# Maduino_Power_Line_Modem_v1_2.net
KiCad netlist of a schematic drawn in EAGLE
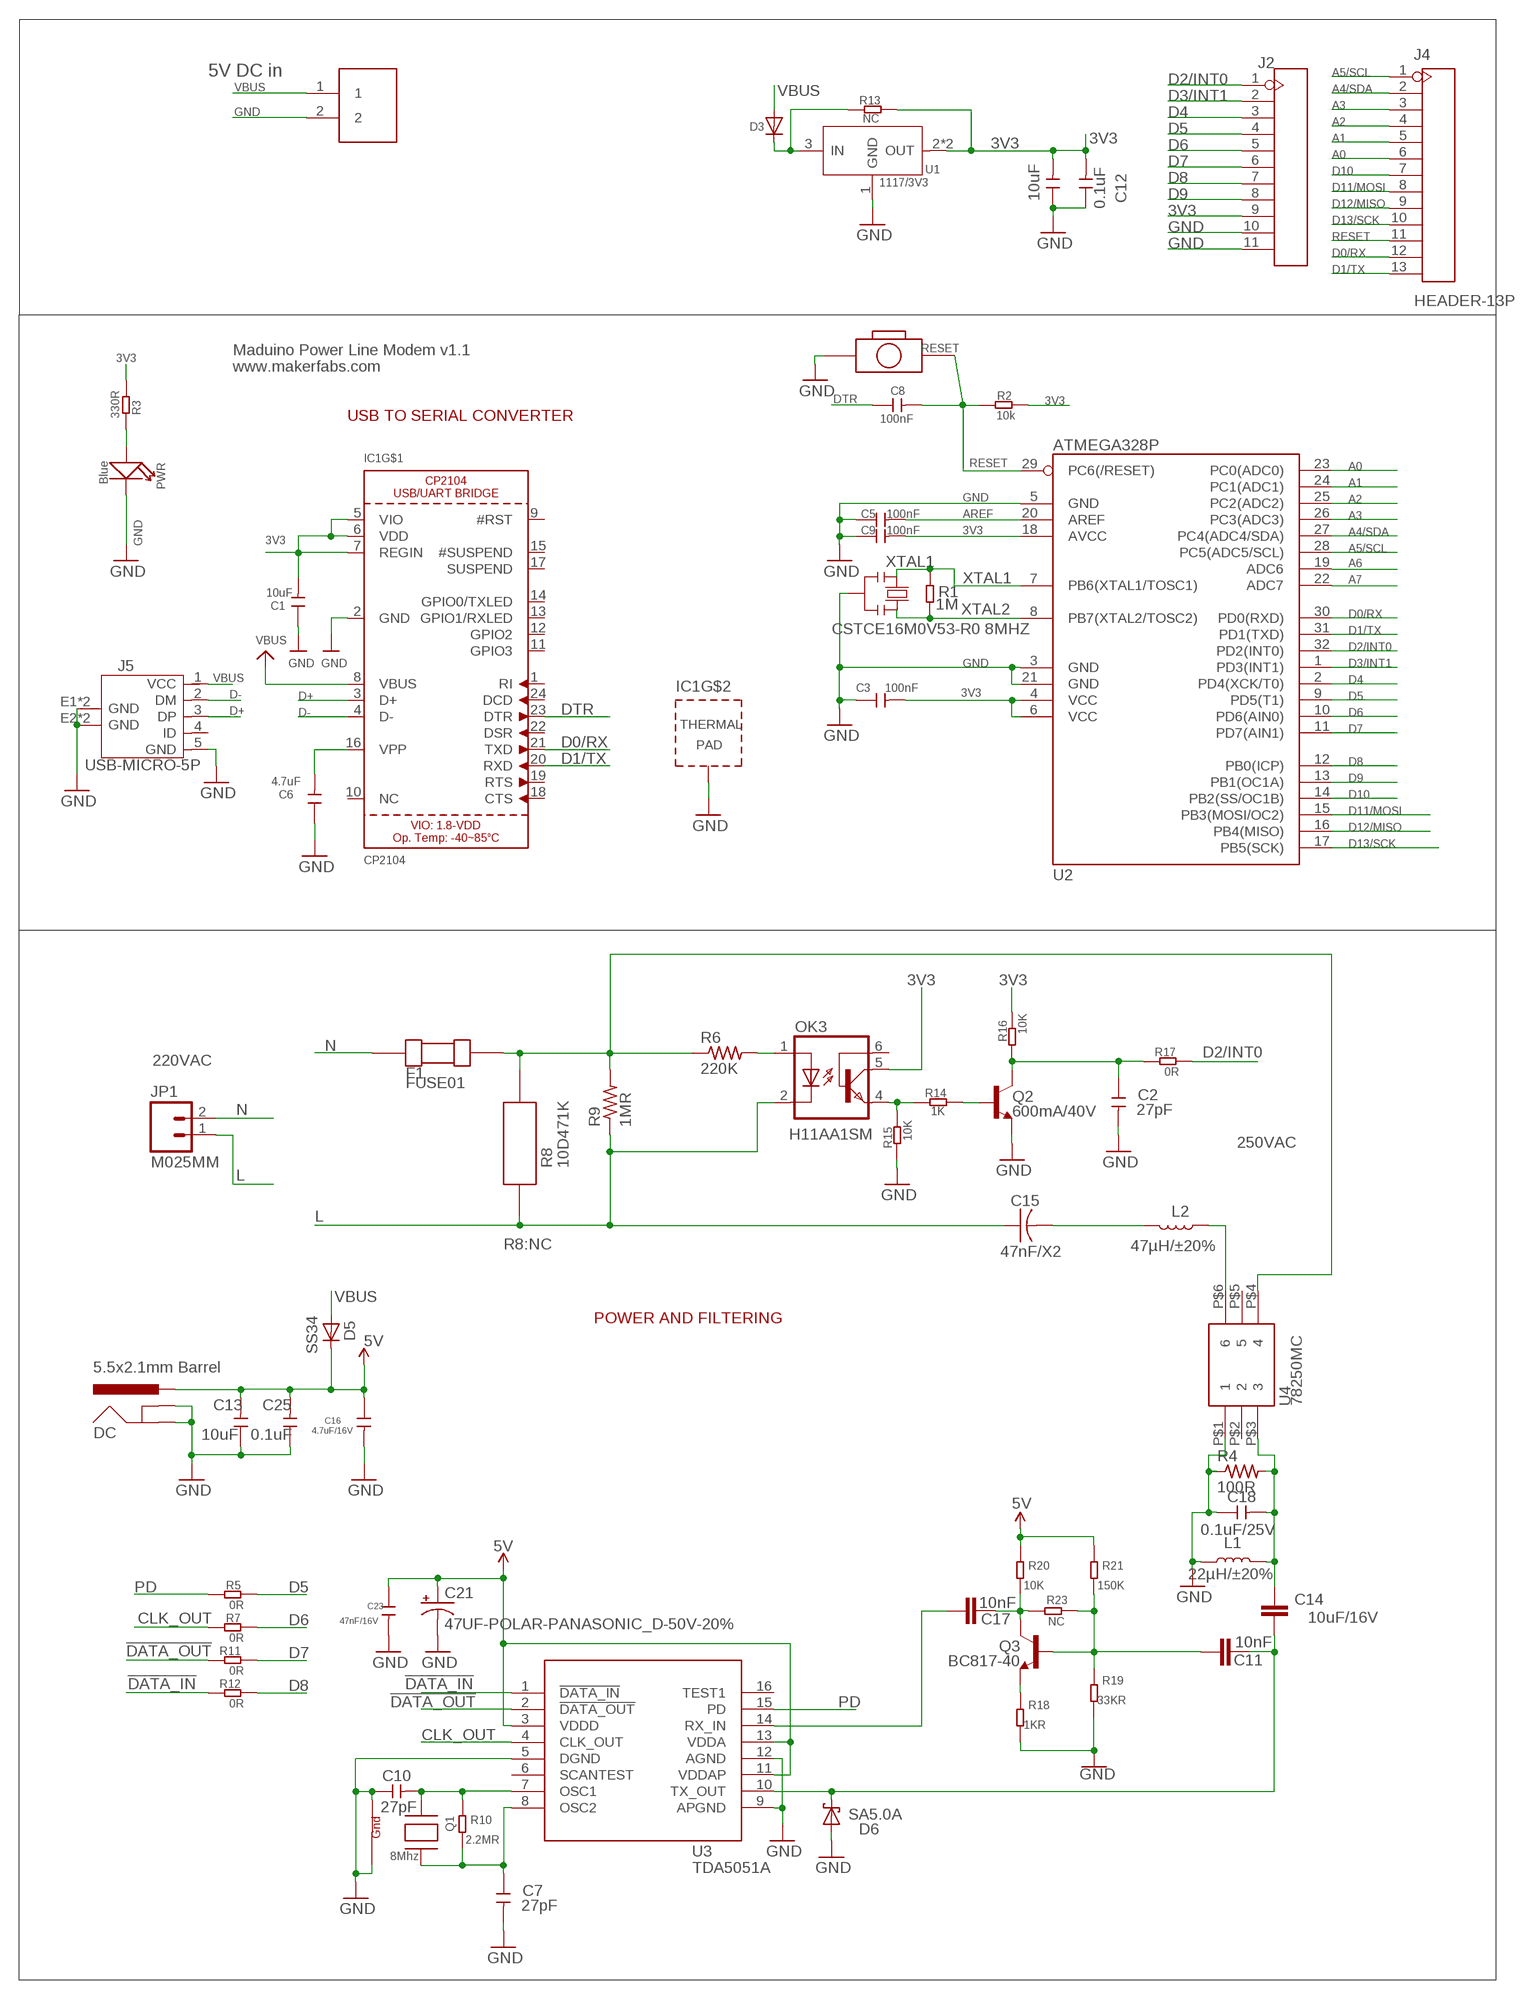
[diagram p0: schematic, sheet 1]

(export (version "E")
  (design (tool "Eeschema 10.0.6"))
  (components
    (comp (ref "C1")
      (value "10uF")
      (footprint "eagle-import:0603")
      (libsource (lib "eagle-import") (part "C-0603"))
    )
    (comp (ref "C2")
      (value "27pF")
      (footprint "eagle-import:0603")
      (libsource (lib "eagle-import") (part "C-0603"))
    )
    (comp (ref "C3")
      (value "100nF")
      (footprint "eagle-import:0603")
      (libsource (lib "eagle-import") (part "C-0603"))
    )
    (comp (ref "C4")
      (value "10uF")
      (footprint "eagle-import:0603")
      (libsource (lib "eagle-import") (part "C-0603"))
    )
    (comp (ref "C5")
      (value "100nF")
      (footprint "eagle-import:0603")
      (libsource (lib "eagle-import") (part "C-0603"))
    )
    (comp (ref "C6")
      (value "4.7uF")
      (footprint "eagle-import:0603")
      (libsource (lib "eagle-import") (part "C-0603"))
    )
    (comp (ref "C7")
      (value "27pF")
      (footprint "eagle-import:0603")
      (libsource (lib "eagle-import") (part "C-0603"))
    )
    (comp (ref "C8")
      (value "100nF")
      (footprint "eagle-import:0603")
      (libsource (lib "eagle-import") (part "C-0603"))
    )
    (comp (ref "C9")
      (value "100nF")
      (footprint "eagle-import:0603")
      (libsource (lib "eagle-import") (part "C-0603"))
    )
    (comp (ref "C10")
      (value "27pF")
      (footprint "eagle-import:0603")
      (libsource (lib "eagle-import") (part "C-0603"))
    )
    (comp (ref "C11")
      (value "10nF")
      (footprint "eagle-import:0603")
      (libsource (lib "eagle-import") (part "10NF-0603-50V-10%"))
    )
    (comp (ref "C12")
      (value "0.1uF")
      (footprint "eagle-import:0603")
      (libsource (lib "eagle-import") (part "C-0603"))
    )
    (comp (ref "C13")
      (value "10uF")
      (footprint "eagle-import:0603")
      (libsource (lib "eagle-import") (part "C-0603"))
    )
    (comp (ref "C14")
      (value "10uF/16V")
      (footprint "eagle-import:0603")
      (fields (field (name "PROD_ID") "CAP-00867"))
      (libsource (lib "eagle-import") (part "10NF-0603-50V-10%"))
    )
    (comp (ref "C15")
      (value "47nF/X2")
      (footprint "eagle-import:C150-054X183")
      (libsource (lib "eagle-import") (part "C-US150-054X183"))
    )
    (comp (ref "C16")
      (value "4.7uF/16V")
      (footprint "eagle-import:0603")
      (libsource (lib "eagle-import") (part "C-0603"))
    )
    (comp (ref "C17")
      (value "10nF")
      (footprint "eagle-import:0603")
      (fields (field (name "PROD_ID") "CAP-00867"))
      (libsource (lib "eagle-import") (part "10NF-0603-50V-10%"))
    )
    (comp (ref "C18")
      (value "0.1uF/25V")
      (footprint "eagle-import:0603")
      (libsource (lib "eagle-import") (part "C-0603"))
    )
    (comp (ref "C21")
      (value "47UF-POLAR-PANASONIC_D-50V-20%")
      (footprint "eagle-import:PANASONIC_D")
      (libsource (lib "eagle-import") (part "47UF-POLAR-PANASONIC_D-50V-20%"))
    )
    (comp (ref "C23")
      (value "47nF/16V")
      (footprint "eagle-import:0603")
      (libsource (lib "eagle-import") (part "C-0603"))
    )
    (comp (ref "C25")
      (value "0.1uF")
      (footprint "eagle-import:0603")
      (libsource (lib "eagle-import") (part "C-0603"))
    )
    (comp (ref "D3")
      (value "DIODESOD-323F")
      (footprint "eagle-import:SOD-323F")
      (libsource (lib "eagle-import") (part "DIODESOD-323F"))
    )
    (comp (ref "D5")
      (value "SS34")
      (footprint "eagle-import:DO-214AC")
      (libsource (lib "eagle-import") (part "DIODE-DO-214AC"))
    )
    (comp (ref "D6")
      (value "SA5.0A")
      (footprint "eagle-import:DO41-10")
      (libsource (lib "eagle-import") (part "SCHOTTKY-DIODEDO41"))
    )
    (comp (ref "DC")
      (value "5.5x2.1mm Barrel")
      (footprint "eagle-import:POWER_JACK_SMD")
      (libsource (lib "eagle-import") (part "POWER_JACKSMD"))
    )
    (comp (ref "F1")
      (value "FUSE01")
      (footprint "eagle-import:FUSE01")
      (libsource (lib "eagle-import") (part "FUSE01"))
    )
    (comp (ref "IC1")
      (value "CP2104")
      (footprint "eagle-import:QFN24_4MM_SMSC")
      (libsource (lib "eagle-import") (part "CP2104"))
    )
    (comp (ref "J1")
      (value "PH2.0-2P-90-DIP")
      (footprint "eagle-import:PH2.0-2P-90-DIP")
      (libsource (lib "eagle-import") (part "PH2.0-2P-90-DIP"))
    )
    (comp (ref "J2")
      (value "HEADER-11P-2.54")
      (footprint "eagle-import:11P-2.54")
      (libsource (lib "eagle-import") (part "HEADER-11P-2.54"))
    )
    (comp (ref "J4")
      (value "HEADER-13P")
      (footprint "eagle-import:13P-2.54")
      (libsource (lib "eagle-import") (part "HEADER-13P"))
    )
    (comp (ref "J5")
      (value "USB-MICRO-5P")
      (footprint "eagle-import:MICRO-USB-5P")
      (libsource (lib "eagle-import") (part "USB-MICRO-5P"))
    )
    (comp (ref "JP1")
      (value "M025MM")
      (footprint "eagle-import:SCREWTERMINAL-5MM-2")
      (fields (field (name "STOREFRONT_ID") "PRT-08432"))
      (libsource (lib "eagle-import") (part "M025MM"))
    )
    (comp (ref "L1")
      (value "22µH/±20%")
      (footprint "eagle-import:CR75")
      (libsource (lib "eagle-import") (part "INDUCTOR-CR75-68UH"))
    )
    (comp (ref "L2")
      (value "47µH/±20%")
      (footprint "eagle-import:CR75")
      (fields (field (name "PROD_ID") "NDUC-09739"))
      (libsource (lib "eagle-import") (part "INDUCTOR-CR75-68UH"))
    )
    (comp (ref "OK3")
      (value "H11A1SM")
      (footprint "eagle-import:DIL6-SMD")
      (libsource (lib "eagle-import") (part "H11A?MS1"))
    )
    (comp (ref "PWR")
      (value "Blue")
      (footprint "eagle-import:LED-0603")
      (libsource (lib "eagle-import") (part "LED'0603'"))
    )
    (comp (ref "Q1")
      (value "8Mhz")
      (footprint "eagle-import:NX3225")
      (libsource (lib "eagle-import") (part "XTAL-4-3225"))
    )
    (comp (ref "Q2")
      (value "600mA/40V")
      (footprint "eagle-import:SOT23-3")
      (libsource (lib "eagle-import") (part "TRANS_NPN-MMBT2222AL"))
    )
    (comp (ref "Q3")
      (value "BC817-40")
      (footprint "eagle-import:SOT23-3")
      (libsource (lib "eagle-import") (part "TRANS_NPN-MMBTA42"))
    )
    (comp (ref "R1")
      (value "1M")
      (footprint "eagle-import:R0603")
      (libsource (lib "eagle-import") (part "R-0603"))
    )
    (comp (ref "R2")
      (value "10k")
      (footprint "eagle-import:R0603")
      (libsource (lib "eagle-import") (part "R-0603"))
    )
    (comp (ref "R3")
      (value "330R")
      (footprint "eagle-import:R0603")
      (libsource (lib "eagle-import") (part "R-0603"))
    )
    (comp (ref "R4")
      (value "100R")
      (footprint "eagle-import:R1206")
      (libsource (lib "eagle-import") (part "R-US_R1206"))
    )
    (comp (ref "R5")
      (value "0R")
      (footprint "eagle-import:R0603")
      (libsource (lib "eagle-import") (part "R-0603"))
    )
    (comp (ref "R6")
      (value "220K")
      (footprint "eagle-import:R1206")
      (libsource (lib "eagle-import") (part "R-US_R1206"))
    )
    (comp (ref "R7")
      (value "0R")
      (footprint "eagle-import:R0603")
      (libsource (lib "eagle-import") (part "R-0603"))
    )
    (comp (ref "R8")
      (value "10D471K")
      (footprint "eagle-import:DIP2-7.5MM")
      (libsource (lib "eagle-import") (part "10D471K"))
    )
    (comp (ref "R9")
      (value "1MR")
      (footprint "eagle-import:R1206")
      (libsource (lib "eagle-import") (part "R-US_R1206"))
    )
    (comp (ref "R10")
      (value "2.2MR")
      (footprint "eagle-import:R0603")
      (libsource (lib "eagle-import") (part "R-0603"))
    )
    (comp (ref "R11")
      (value "0R")
      (footprint "eagle-import:R0603")
      (libsource (lib "eagle-import") (part "R-0603"))
    )
    (comp (ref "R12")
      (value "0R")
      (footprint "eagle-import:R0603")
      (libsource (lib "eagle-import") (part "R-0603"))
    )
    (comp (ref "R13")
      (value "NC")
      (footprint "eagle-import:R0603")
      (libsource (lib "eagle-import") (part "R-0603"))
    )
    (comp (ref "R14")
      (value "1K")
      (footprint "eagle-import:R0603")
      (libsource (lib "eagle-import") (part "R-0603"))
    )
    (comp (ref "R15")
      (value "10K")
      (footprint "eagle-import:R0603")
      (libsource (lib "eagle-import") (part "R-0603"))
    )
    (comp (ref "R16")
      (value "10K")
      (footprint "eagle-import:R0603")
      (libsource (lib "eagle-import") (part "R-0603"))
    )
    (comp (ref "R17")
      (value "0R")
      (footprint "eagle-import:R0603")
      (libsource (lib "eagle-import") (part "R-0603"))
    )
    (comp (ref "R18")
      (value "1KR")
      (footprint "eagle-import:R0603")
      (libsource (lib "eagle-import") (part "R-0603"))
    )
    (comp (ref "R19")
      (value "33KR")
      (footprint "eagle-import:R0603")
      (libsource (lib "eagle-import") (part "R-0603"))
    )
    (comp (ref "R20")
      (value "10K")
      (footprint "eagle-import:R0603")
      (libsource (lib "eagle-import") (part "R-0603"))
    )
    (comp (ref "R21")
      (value "150K")
      (footprint "eagle-import:R0603")
      (libsource (lib "eagle-import") (part "R-0603"))
    )
    (comp (ref "R23")
      (value "NC")
      (footprint "eagle-import:R0603")
      (libsource (lib "eagle-import") (part "R-0603"))
    )
    (comp (ref "RESET")
      (value "BOTTON-2P-90D")
      (footprint "eagle-import:2P-7.62X3.56-90D")
      (libsource (lib "eagle-import") (part "BOTTON-2P-90D"))
    )
    (comp (ref "U1")
      (value "1117/3V3")
      (footprint "eagle-import:SOT89")
      (libsource (lib "eagle-import") (part "LD1117'SOT89'"))
    )
    (comp (ref "U2")
      (value "ATMEGA328P")
      (footprint "eagle-import:TQFP32")
      (libsource (lib "eagle-import") (part "ATMEGA8/168/328"))
    )
    (comp (ref "U3")
      (value "TDA5051A")
      (footprint "eagle-import:SOT-162")
      (libsource (lib "eagle-import") (part "TDA5051A"))
    )
    (comp (ref "U4")
      (value "78250MC")
      (footprint "eagle-import:SMD6-254-1270X900")
      (libsource (lib "eagle-import") (part "78250MC"))
    )
    (comp (ref "Y1")
      (value "CSTCE16M0V53-R0 8MHZ")
      (footprint "eagle-import:RESONATOR")
      (libsource (lib "eagle-import") (part "RESONATORMU"))
    )
  )
  (nets
    (net (code "1") (name "/3V3") (class "Default")
      (node (ref "C1") (pin "2") (pinfunction "2_2") (pintype "passive"))
      (node (ref "C12") (pin "2") (pinfunction "2_2") (pintype "passive"))
      (node (ref "C3") (pin "2") (pinfunction "2_2") (pintype "passive"))
      (node (ref "C4") (pin "2") (pinfunction "2_2") (pintype "passive"))
      (node (ref "C9") (pin "2") (pinfunction "2_2") (pintype "passive"))
      (node (ref "IC1") (pin "5") (pinfunction "VIO_5") (pintype "power_in"))
      (node (ref "IC1") (pin "6") (pinfunction "VDD_6") (pintype "power_in"))
      (node (ref "IC1") (pin "7") (pinfunction "REGIN_7") (pintype "power_in"))
      (node (ref "J2") (pin "9") (pinfunction "9_9") (pintype "bidirectional"))
      (node (ref "OK3") (pin "5") (pinfunction "COL_5") (pintype "passive"))
      (node (ref "R13") (pin "1") (pinfunction "1_1") (pintype "passive"))
      (node (ref "R16") (pin "1") (pinfunction "1_1") (pintype "passive"))
      (node (ref "R2") (pin "1") (pinfunction "1_1") (pintype "passive"))
      (node (ref "R3") (pin "1") (pinfunction "1_1") (pintype "passive"))
      (node (ref "U1") (pin "2") (pinfunction "OUT_2") (pintype "bidirectional"))
      (node (ref "U1") (pin "4") (pinfunction "OUT_4") (pintype "bidirectional"))
      (node (ref "U2") (pin "18") (pinfunction "AVCC_18") (pintype "bidirectional"))
      (node (ref "U2") (pin "4") (pinfunction "VCC_4") (pintype "bidirectional"))
      (node (ref "U2") (pin "6") (pinfunction "VCC_6") (pintype "bidirectional"))
    )
    (net (code "2") (name "/A0") (class "Default")
      (node (ref "J4") (pin "6") (pinfunction "6_6") (pintype "bidirectional"))
      (node (ref "U2") (pin "23") (pinfunction "PC0(ADC0)_23") (pintype "bidirectional"))
    )
    (net (code "3") (name "/A1") (class "Default")
      (node (ref "J4") (pin "5") (pinfunction "5_5") (pintype "bidirectional"))
      (node (ref "U2") (pin "24") (pinfunction "PC1(ADC1)_24") (pintype "bidirectional"))
    )
    (net (code "4") (name "/A2") (class "Default")
      (node (ref "J4") (pin "4") (pinfunction "4_4") (pintype "bidirectional"))
      (node (ref "U2") (pin "25") (pinfunction "PC2(ADC2)_25") (pintype "bidirectional"))
    )
    (net (code "5") (name "/A3") (class "Default")
      (node (ref "J4") (pin "3") (pinfunction "3_3") (pintype "bidirectional"))
      (node (ref "U2") (pin "26") (pinfunction "PC3(ADC3)_26") (pintype "bidirectional"))
    )
    (net (code "6") (name "/A4{slash}SDA") (class "Default")
      (node (ref "J4") (pin "2") (pinfunction "2_2") (pintype "bidirectional"))
      (node (ref "U2") (pin "27") (pinfunction "PC4(ADC4/SDA)_27") (pintype "bidirectional"))
    )
    (net (code "7") (name "/A5{slash}SCL") (class "Default")
      (node (ref "J4") (pin "1") (pinfunction "1_1") (pintype "bidirectional"))
      (node (ref "U2") (pin "28") (pinfunction "PC5(ADC5/SCL)_28") (pintype "bidirectional"))
    )
    (net (code "8") (name "/A6") (class "Default")
      (node (ref "U2") (pin "19") (pinfunction "ADC6_19") (pintype "bidirectional"))
    )
    (net (code "9") (name "/A7") (class "Default")
      (node (ref "U2") (pin "22") (pinfunction "ADC7_22") (pintype "bidirectional"))
    )
    (net (code "10") (name "/AREF") (class "Default")
      (node (ref "C5") (pin "2") (pinfunction "2_2") (pintype "passive"))
      (node (ref "U2") (pin "20") (pinfunction "AREF_20") (pintype "bidirectional"))
    )
    (net (code "11") (name "/CLK_OUT") (class "Default")
      (node (ref "R7") (pin "2") (pinfunction "2_2") (pintype "passive"))
      (node (ref "U3") (pin "4") (pinfunction "CLK_OUT_4") (pintype "bidirectional"))
    )
    (net (code "12") (name "/D+") (class "Default")
      (node (ref "IC1") (pin "3") (pinfunction "D+_3") (pintype "bidirectional"))
      (node (ref "J5") (pin "3") (pinfunction "DP_3") (pintype "bidirectional"))
    )
    (net (code "13") (name "/D-") (class "Default")
      (node (ref "IC1") (pin "4") (pinfunction "D-_4") (pintype "bidirectional"))
      (node (ref "J5") (pin "2") (pinfunction "DM_2") (pintype "bidirectional"))
    )
    (net (code "14") (name "/D0{slash}RX") (class "Default")
      (node (ref "IC1") (pin "21") (pinfunction "TXD_21") (pintype "output"))
      (node (ref "J4") (pin "12") (pinfunction "12_12") (pintype "bidirectional"))
      (node (ref "U2") (pin "30") (pinfunction "PD0(RXD)_30") (pintype "bidirectional"))
    )
    (net (code "15") (name "/D1{slash}TX") (class "Default")
      (node (ref "IC1") (pin "20") (pinfunction "RXD_20") (pintype "input"))
      (node (ref "J4") (pin "13") (pinfunction "13_13") (pintype "bidirectional"))
      (node (ref "U2") (pin "31") (pinfunction "PD1(TXD)_31") (pintype "bidirectional"))
    )
    (net (code "16") (name "/D2{slash}INT0") (class "Default")
      (node (ref "J2") (pin "1") (pinfunction "1_1") (pintype "bidirectional"))
      (node (ref "R17") (pin "1") (pinfunction "1_1") (pintype "passive"))
      (node (ref "U2") (pin "32") (pinfunction "PD2(INT0)_32") (pintype "bidirectional"))
    )
    (net (code "17") (name "/D3{slash}INT1") (class "Default")
      (node (ref "J2") (pin "2") (pinfunction "2_2") (pintype "bidirectional"))
      (node (ref "U2") (pin "1") (pinfunction "PD3(INT1)_1") (pintype "bidirectional"))
    )
    (net (code "18") (name "/D4") (class "Default")
      (node (ref "J2") (pin "3") (pinfunction "3_3") (pintype "bidirectional"))
      (node (ref "U2") (pin "2") (pinfunction "PD4(XCK/T0)_2") (pintype "bidirectional"))
    )
    (net (code "19") (name "/D5") (class "Default")
      (node (ref "J2") (pin "4") (pinfunction "4_4") (pintype "bidirectional"))
      (node (ref "R5") (pin "1") (pinfunction "1_1") (pintype "passive"))
      (node (ref "U2") (pin "9") (pinfunction "PD5(T1)_9") (pintype "bidirectional"))
    )
    (net (code "20") (name "/D6") (class "Default")
      (node (ref "J2") (pin "5") (pinfunction "5_5") (pintype "bidirectional"))
      (node (ref "R7") (pin "1") (pinfunction "1_1") (pintype "passive"))
      (node (ref "U2") (pin "10") (pinfunction "PD6(AIN0)_10") (pintype "bidirectional"))
    )
    (net (code "21") (name "/D7") (class "Default")
      (node (ref "J2") (pin "6") (pinfunction "6_6") (pintype "bidirectional"))
      (node (ref "R11") (pin "1") (pinfunction "1_1") (pintype "passive"))
      (node (ref "U2") (pin "11") (pinfunction "PD7(AIN1)_11") (pintype "bidirectional"))
    )
    (net (code "22") (name "/D8") (class "Default")
      (node (ref "J2") (pin "7") (pinfunction "7_7") (pintype "bidirectional"))
      (node (ref "R12") (pin "1") (pinfunction "1_1") (pintype "passive"))
      (node (ref "U2") (pin "12") (pinfunction "PB0(ICP)_12") (pintype "bidirectional"))
    )
    (net (code "23") (name "/D9") (class "Default")
      (node (ref "J2") (pin "8") (pinfunction "8_8") (pintype "bidirectional"))
      (node (ref "U2") (pin "13") (pinfunction "PB1(OC1A)_13") (pintype "bidirectional"))
    )
    (net (code "24") (name "/D10") (class "Default")
      (node (ref "J4") (pin "7") (pinfunction "7_7") (pintype "bidirectional"))
      (node (ref "U2") (pin "14") (pinfunction "PB2(SS/OC1B)_14") (pintype "bidirectional"))
    )
    (net (code "25") (name "/D11{slash}MOSI") (class "Default")
      (node (ref "J4") (pin "8") (pinfunction "8_8") (pintype "bidirectional"))
      (node (ref "U2") (pin "15") (pinfunction "PB3(MOSI/OC2)_15") (pintype "bidirectional"))
    )
    (net (code "26") (name "/D12{slash}MISO") (class "Default")
      (node (ref "J4") (pin "9") (pinfunction "9_9") (pintype "bidirectional"))
      (node (ref "U2") (pin "16") (pinfunction "PB4(MISO)_16") (pintype "bidirectional"))
    )
    (net (code "27") (name "/D13{slash}SCK") (class "Default")
      (node (ref "J4") (pin "10") (pinfunction "10_10") (pintype "bidirectional"))
      (node (ref "U2") (pin "17") (pinfunction "PB5(SCK)_17") (pintype "bidirectional"))
    )
    (net (code "28") (name "/DTR") (class "Default")
      (node (ref "C8") (pin "1") (pinfunction "1_1") (pintype "passive"))
      (node (ref "IC1") (pin "23") (pinfunction "DTR_23") (pintype "output"))
    )
    (net (code "29") (name "/L") (class "Default")
      (node (ref "C15") (pin "1") (pinfunction "1_1") (pintype "passive"))
      (node (ref "JP1") (pin "1") (pinfunction "1_1") (pintype "passive"))
      (node (ref "OK3") (pin "2") (pinfunction "C_2") (pintype "passive"))
      (node (ref "R8") (pin "P$2") (pinfunction "2_P$2") (pintype "bidirectional"))
      (node (ref "R9") (pin "1") (pinfunction "1_1") (pintype "passive"))
    )
    (net (code "30") (name "/N") (class "Default")
      (node (ref "F1") (pin "P$1") (pinfunction "P$1_P$1") (pintype "bidirectional"))
      (node (ref "JP1") (pin "2") (pinfunction "2_2") (pintype "passive"))
    )
    (net (code "31") (name "/PD") (class "Default")
      (node (ref "R5") (pin "2") (pinfunction "2_2") (pintype "passive"))
      (node (ref "U3") (pin "15") (pinfunction "PD_15") (pintype "bidirectional"))
    )
    (net (code "32") (name "/RESET") (class "Default")
      (node (ref "C8") (pin "2") (pinfunction "2_2") (pintype "passive"))
      (node (ref "J4") (pin "11") (pinfunction "11_11") (pintype "bidirectional"))
      (node (ref "R2") (pin "2") (pinfunction "2_2") (pintype "passive"))
      (node (ref "RESET") (pin "P$1") (pinfunction "1_P$1") (pintype "bidirectional"))
      (node (ref "U2") (pin "29") (pinfunction "PC6(/RESET)_29") (pintype "bidirectional"))
    )
    (net (code "33") (name "/XTAL1") (class "Default")
      (node (ref "R1") (pin "2") (pinfunction "2_2") (pintype "passive"))
      (node (ref "U2") (pin "7") (pinfunction "PB6(XTAL1/TOSC1)_7") (pintype "bidirectional"))
      (node (ref "Y1") (pin "1") (pinfunction "1_1") (pintype "passive"))
    )
    (net (code "34") (name "/XTAL2") (class "Default")
      (node (ref "R1") (pin "1") (pinfunction "1_1") (pintype "passive"))
      (node (ref "U2") (pin "8") (pinfunction "PB7(XTAL2/TOSC2)_8") (pintype "bidirectional"))
      (node (ref "Y1") (pin "3") (pinfunction "3_3") (pintype "passive"))
    )
    (net (code "35") (name "/~{DATA_IN}") (class "Default")
      (node (ref "R12") (pin "2") (pinfunction "2_2") (pintype "passive"))
      (node (ref "U3") (pin "1") (pinfunction "~{DATA_IN}_1") (pintype "bidirectional"))
    )
    (net (code "36") (name "/~{DATA_OUT}") (class "Default")
      (node (ref "R11") (pin "2") (pinfunction "2_2") (pintype "passive"))
      (node (ref "U3") (pin "2") (pinfunction "~{DATA_OUT}_2") (pintype "bidirectional"))
    )
    (net (code "37") (name "5V") (class "Default")
      (node (ref "C13") (pin "2") (pinfunction "2_2") (pintype "passive"))
      (node (ref "C16") (pin "1") (pinfunction "1_1") (pintype "passive"))
      (node (ref "C21") (pin "+") (pinfunction "+_+") (pintype "passive"))
      (node (ref "C23") (pin "1") (pinfunction "1_1") (pintype "passive"))
      (node (ref "C25") (pin "2") (pinfunction "2_2") (pintype "passive"))
      (node (ref "D5") (pin "C") (pinfunction "C_C") (pintype "passive"))
      (node (ref "DC") (pin "VIN0") (pinfunction "PWR_VIN0") (pintype "bidirectional"))
      (node (ref "R20") (pin "1") (pinfunction "1_1") (pintype "passive"))
      (node (ref "R21") (pin "1") (pinfunction "1_1") (pintype "passive"))
      (node (ref "U3") (pin "11") (pinfunction "VDDAP_11") (pintype "bidirectional"))
      (node (ref "U3") (pin "13") (pinfunction "VDDA_13") (pintype "bidirectional"))
      (node (ref "U3") (pin "3") (pinfunction "VDDD_3") (pintype "bidirectional"))
    )
    (net (code "38") (name "GND") (class "Default")
      (node (ref "C1") (pin "1") (pinfunction "1_1") (pintype "passive"))
      (node (ref "C10") (pin "1") (pinfunction "1_1") (pintype "passive"))
      (node (ref "C12") (pin "1") (pinfunction "1_1") (pintype "passive"))
      (node (ref "C13") (pin "1") (pinfunction "1_1") (pintype "passive"))
      (node (ref "C16") (pin "2") (pinfunction "2_2") (pintype "passive"))
      (node (ref "C18") (pin "1") (pinfunction "1_1") (pintype "passive"))
      (node (ref "C2") (pin "2") (pinfunction "2_2") (pintype "passive"))
      (node (ref "C21") (pin "-") (pinfunction "-_-") (pintype "passive"))
      (node (ref "C23") (pin "2") (pinfunction "2_2") (pintype "passive"))
      (node (ref "C25") (pin "1") (pinfunction "1_1") (pintype "passive"))
      (node (ref "C3") (pin "1") (pinfunction "1_1") (pintype "passive"))
      (node (ref "C4") (pin "1") (pinfunction "1_1") (pintype "passive"))
      (node (ref "C5") (pin "1") (pinfunction "1_1") (pintype "passive"))
      (node (ref "C6") (pin "1") (pinfunction "1_1") (pintype "passive"))
      (node (ref "C7") (pin "2") (pinfunction "2_2") (pintype "passive"))
      (node (ref "C9") (pin "1") (pinfunction "1_1") (pintype "passive"))
      (node (ref "D6") (pin "A") (pinfunction "A_A") (pintype "passive"))
      (node (ref "DC") (pin "GND") (pinfunction "GNDBREAK_GND") (pintype "bidirectional"))
      (node (ref "DC") (pin "P$4") (pinfunction "GND_P$4") (pintype "bidirectional"))
      (node (ref "IC1") (pin "2") (pinfunction "GND_2") (pintype "power_in"))
      (node (ref "IC1") (pin "THERM") (pinfunction "TP_THERM") (pintype "power_in"))
      (node (ref "J1") (pin "2") (pinfunction "2_2") (pintype "bidirectional"))
      (node (ref "J2") (pin "10") (pinfunction "10_10") (pintype "bidirectional"))
      (node (ref "J2") (pin "11") (pinfunction "11_11") (pintype "bidirectional"))
      (node (ref "J5") (pin "5") (pinfunction "GND_5") (pintype "bidirectional"))
      (node (ref "J5") (pin "E1") (pinfunction "GND_E1") (pintype "bidirectional"))
      (node (ref "J5") (pin "E2") (pinfunction "GND_E2") (pintype "bidirectional"))
      (node (ref "J5") (pin "P1") (pinfunction "GND_P1") (pintype "bidirectional"))
      (node (ref "J5") (pin "P2") (pinfunction "GND_P2") (pintype "bidirectional"))
      (node (ref "L1") (pin "P$1") (pinfunction "1_P$1") (pintype "passive"))
      (node (ref "PWR") (pin "-") (pinfunction "-_-") (pintype "passive"))
      (node (ref "Q1") (pin "2") (pinfunction "G2_2") (pintype "power_in"))
      (node (ref "Q1") (pin "4") (pinfunction "G1_4") (pintype "power_in"))
      (node (ref "Q2") (pin "2") (pinfunction "E_2") (pintype "passive"))
      (node (ref "R15") (pin "2") (pinfunction "2_2") (pintype "passive"))
      (node (ref "R18") (pin "2") (pinfunction "2_2") (pintype "passive"))
      (node (ref "R19") (pin "2") (pinfunction "2_2") (pintype "passive"))
      (node (ref "R4") (pin "1") (pinfunction "1_1") (pintype "passive"))
      (node (ref "RESET") (pin "P$2") (pinfunction "2_P$2") (pintype "bidirectional"))
      (node (ref "U1") (pin "1") (pinfunction "GND_1") (pintype "bidirectional"))
      (node (ref "U2") (pin "21") (pinfunction "GND_21") (pintype "bidirectional"))
      (node (ref "U2") (pin "3") (pinfunction "GND_3") (pintype "bidirectional"))
      (node (ref "U2") (pin "5") (pinfunction "GND_5") (pintype "bidirectional"))
      (node (ref "U3") (pin "12") (pinfunction "AGND_12") (pintype "bidirectional"))
      (node (ref "U3") (pin "5") (pinfunction "DGND_5") (pintype "bidirectional"))
      (node (ref "U3") (pin "9") (pinfunction "APGND_9") (pintype "bidirectional"))
      (node (ref "U4") (pin "P$1") (pinfunction "1_P$1") (pintype "bidirectional"))
      (node (ref "Y1") (pin "2") (pinfunction "2_2") (pintype "passive"))
    )
    (net (code "39") (name "Net-(IC1A-VPP)") (class "Default")
      (node (ref "C6") (pin "2") (pinfunction "2_2") (pintype "passive"))
      (node (ref "IC1") (pin "16") (pinfunction "VPP_16") (pintype "bidirectional"))
    )
    (net (code "40") (name "Net-(L1-2)") (class "Default")
      (node (ref "C14") (pin "1") (pinfunction "1_1") (pintype "passive"))
      (node (ref "C18") (pin "2") (pinfunction "2_2") (pintype "passive"))
      (node (ref "L1") (pin "P$2") (pinfunction "2_P$2") (pintype "passive"))
      (node (ref "R4") (pin "2") (pinfunction "2_2") (pintype "passive"))
      (node (ref "U4") (pin "P$3") (pinfunction "3_P$3") (pintype "bidirectional"))
    )
    (net (code "41") (name "Net-(L2-1)") (class "Default")
      (node (ref "L2") (pin "P$1") (pinfunction "1_P$1") (pintype "passive"))
      (node (ref "U4") (pin "P$6") (pinfunction "6_P$6") (pintype "bidirectional"))
    )
    (net (code "42") (name "Net-(L2-2)") (class "Default")
      (node (ref "C15") (pin "2") (pinfunction "2_2") (pintype "passive"))
      (node (ref "L2") (pin "P$2") (pinfunction "2_P$2") (pintype "passive"))
    )
    (net (code "43") (name "Net-(OK3-A)") (class "Default")
      (node (ref "OK3") (pin "1") (pinfunction "A_1") (pintype "passive"))
      (node (ref "R6") (pin "2") (pinfunction "2_2") (pintype "passive"))
    )
    (net (code "44") (name "Net-(OK3-EMI)") (class "Default")
      (node (ref "OK3") (pin "4") (pinfunction "EMI_4") (pintype "passive"))
      (node (ref "R14") (pin "2") (pinfunction "2_2") (pintype "passive"))
      (node (ref "R15") (pin "1") (pinfunction "1_1") (pintype "passive"))
    )
    (net (code "45") (name "Net-(PWR-Pad+)") (class "Default")
      (node (ref "PWR") (pin "+") (pinfunction "+_+") (pintype "passive"))
      (node (ref "R3") (pin "2") (pinfunction "2_2") (pintype "passive"))
    )
    (net (code "46") (name "Net-(Q1-X1)") (class "Default")
      (node (ref "C10") (pin "2") (pinfunction "2_2") (pintype "passive"))
      (node (ref "Q1") (pin "1") (pinfunction "X1_1") (pintype "bidirectional"))
      (node (ref "R10") (pin "1") (pinfunction "1_1") (pintype "passive"))
      (node (ref "U3") (pin "7") (pinfunction "OSC1_7") (pintype "bidirectional"))
    )
    (net (code "47") (name "Net-(Q1-X2)") (class "Default")
      (node (ref "C7") (pin "1") (pinfunction "1_1") (pintype "passive"))
      (node (ref "Q1") (pin "3") (pinfunction "X2_3") (pintype "bidirectional"))
      (node (ref "R10") (pin "2") (pinfunction "2_2") (pintype "passive"))
      (node (ref "U3") (pin "8") (pinfunction "OSC2_8") (pintype "bidirectional"))
    )
    (net (code "48") (name "Net-(Q2-B)") (class "Default")
      (node (ref "Q2") (pin "1") (pinfunction "B_1") (pintype "passive"))
      (node (ref "R14") (pin "1") (pinfunction "1_1") (pintype "passive"))
    )
    (net (code "49") (name "Net-(Q2-C)") (class "Default")
      (node (ref "C2") (pin "1") (pinfunction "1_1") (pintype "passive"))
      (node (ref "Q2") (pin "3") (pinfunction "C_3") (pintype "passive"))
      (node (ref "R16") (pin "2") (pinfunction "2_2") (pintype "passive"))
      (node (ref "R17") (pin "2") (pinfunction "2_2") (pintype "passive"))
    )
    (net (code "50") (name "Net-(Q3-B)") (class "Default")
      (node (ref "C11") (pin "2") (pinfunction "2_2") (pintype "passive"))
      (node (ref "Q3") (pin "1") (pinfunction "B_1") (pintype "passive"))
      (node (ref "R19") (pin "1") (pinfunction "1_1") (pintype "passive"))
      (node (ref "R21") (pin "2") (pinfunction "2_2") (pintype "passive"))
      (node (ref "R23") (pin "2") (pinfunction "2_2") (pintype "passive"))
    )
    (net (code "51") (name "Net-(Q3-C)") (class "Default")
      (node (ref "C17") (pin "1") (pinfunction "1_1") (pintype "passive"))
      (node (ref "Q3") (pin "3") (pinfunction "C_3") (pintype "passive"))
      (node (ref "R20") (pin "2") (pinfunction "2_2") (pintype "passive"))
      (node (ref "R23") (pin "1") (pinfunction "1_1") (pintype "passive"))
    )
    (net (code "52") (name "Net-(Q3-E)") (class "Default")
      (node (ref "Q3") (pin "2") (pinfunction "E_2") (pintype "passive"))
      (node (ref "R18") (pin "1") (pinfunction "1_1") (pintype "passive"))
    )
    (net (code "53") (name "Net-(R8-1)") (class "Default")
      (node (ref "F1") (pin "P$2") (pinfunction "P$2_P$2") (pintype "bidirectional"))
      (node (ref "R6") (pin "1") (pinfunction "1_1") (pintype "passive"))
      (node (ref "R8") (pin "P$1") (pinfunction "1_P$1") (pintype "bidirectional"))
      (node (ref "R9") (pin "2") (pinfunction "2_2") (pintype "passive"))
      (node (ref "U4") (pin "P$4") (pinfunction "4_P$4") (pintype "bidirectional"))
    )
    (net (code "54") (name "Net-(U1-IN)") (class "Default")
      (node (ref "D3") (pin "C") (pinfunction "C_C") (pintype "passive"))
      (node (ref "R13") (pin "2") (pinfunction "2_2") (pintype "passive"))
      (node (ref "U1") (pin "3") (pinfunction "IN_3") (pintype "bidirectional"))
    )
    (net (code "55") (name "Net-(U3-RX_IN)") (class "Default")
      (node (ref "C17") (pin "2") (pinfunction "2_2") (pintype "passive"))
      (node (ref "U3") (pin "14") (pinfunction "RX_IN_14") (pintype "bidirectional"))
    )
    (net (code "56") (name "Net-(U3-TX_OUT)") (class "Default")
      (node (ref "C11") (pin "1") (pinfunction "1_1") (pintype "passive"))
      (node (ref "C14") (pin "2") (pinfunction "2_2") (pintype "passive"))
      (node (ref "D6") (pin "C") (pinfunction "C_C") (pintype "passive"))
      (node (ref "U3") (pin "10") (pinfunction "TX_OUT_10") (pintype "bidirectional"))
    )
    (net (code "57") (name "VBUS") (class "Default")
      (node (ref "D3") (pin "A") (pinfunction "A_A") (pintype "passive"))
      (node (ref "D5") (pin "A") (pinfunction "A_A") (pintype "passive"))
      (node (ref "IC1") (pin "8") (pinfunction "VBUS_8") (pintype "power_in"))
      (node (ref "J1") (pin "1") (pinfunction "1_1") (pintype "bidirectional"))
      (node (ref "J5") (pin "1") (pinfunction "VCC_1") (pintype "bidirectional"))
    )
    (net (code "58") (name "unconnected-(IC1A-#RST-Pad9)") (class "Default")
      (node (ref "IC1") (pin "9") (pinfunction "#RST_9") (pintype "bidirectional"))
    )
    (net (code "59") (name "unconnected-(IC1A-#SUSPEND-Pad15)") (class "Default")
      (node (ref "IC1") (pin "15") (pinfunction "#SUSPEND_15") (pintype "output"))
    )
    (net (code "60") (name "unconnected-(IC1A-CTS-Pad18)") (class "Default")
      (node (ref "IC1") (pin "18") (pinfunction "CTS_18") (pintype "input"))
    )
    (net (code "61") (name "unconnected-(IC1A-DCD-Pad24)") (class "Default")
      (node (ref "IC1") (pin "24") (pinfunction "DCD_24") (pintype "input"))
    )
    (net (code "62") (name "unconnected-(IC1A-DSR-Pad22)") (class "Default")
      (node (ref "IC1") (pin "22") (pinfunction "DSR_22") (pintype "input"))
    )
    (net (code "63") (name "unconnected-(IC1A-GPIO0{slash}TXLED-Pad14)") (class "Default")
      (node (ref "IC1") (pin "14") (pinfunction "GPIO0/TXLED_14") (pintype "bidirectional"))
    )
    (net (code "64") (name "unconnected-(IC1A-GPIO1{slash}RXLED-Pad13)") (class "Default")
      (node (ref "IC1") (pin "13") (pinfunction "GPIO1/RXLED_13") (pintype "bidirectional"))
    )
    (net (code "65") (name "unconnected-(IC1A-GPIO2-Pad12)") (class "Default")
      (node (ref "IC1") (pin "12") (pinfunction "GPIO2_12") (pintype "bidirectional"))
    )
    (net (code "66") (name "unconnected-(IC1A-GPIO3-Pad11)") (class "Default")
      (node (ref "IC1") (pin "11") (pinfunction "GPIO3_11") (pintype "bidirectional"))
    )
    (net (code "67") (name "unconnected-(IC1A-NC-Pad10)") (class "Default")
      (node (ref "IC1") (pin "10") (pinfunction "NC_10") (pintype "no_connect"))
    )
    (net (code "68") (name "unconnected-(IC1A-RI-Pad1)") (class "Default")
      (node (ref "IC1") (pin "1") (pinfunction "RI_1") (pintype "input"))
    )
    (net (code "69") (name "unconnected-(IC1A-RTS-Pad19)") (class "Default")
      (node (ref "IC1") (pin "19") (pinfunction "RTS_19") (pintype "output"))
    )
    (net (code "70") (name "unconnected-(IC1A-SUSPEND-Pad17)") (class "Default")
      (node (ref "IC1") (pin "17") (pinfunction "SUSPEND_17") (pintype "output"))
    )
    (net (code "71") (name "unconnected-(J5-ID-Pad4)") (class "Default")
      (node (ref "J5") (pin "4") (pinfunction "ID_4") (pintype "bidirectional"))
    )
    (net (code "72") (name "unconnected-(OK3-BAS-Pad6)") (class "Default")
      (node (ref "OK3") (pin "6") (pinfunction "BAS_6") (pintype "passive"))
    )
    (net (code "73") (name "unconnected-(U3-SCANTEST-Pad6)") (class "Default")
      (node (ref "U3") (pin "6") (pinfunction "SCANTEST_6") (pintype "bidirectional"))
    )
    (net (code "74") (name "unconnected-(U3-TEST1-Pad16)") (class "Default")
      (node (ref "U3") (pin "16") (pinfunction "TEST1_16") (pintype "bidirectional"))
    )
    (net (code "75") (name "unconnected-(U4-2-PadP$2)") (class "Default")
      (node (ref "U4") (pin "P$2") (pinfunction "2_P$2") (pintype "bidirectional"))
    )
    (net (code "76") (name "unconnected-(U4-5-PadP$5)") (class "Default")
      (node (ref "U4") (pin "P$5") (pinfunction "5_P$5") (pintype "bidirectional"))
    )
  )
)
